# LMS7002M.net
KiCad netlist of a schematic drawn in Altium Designer
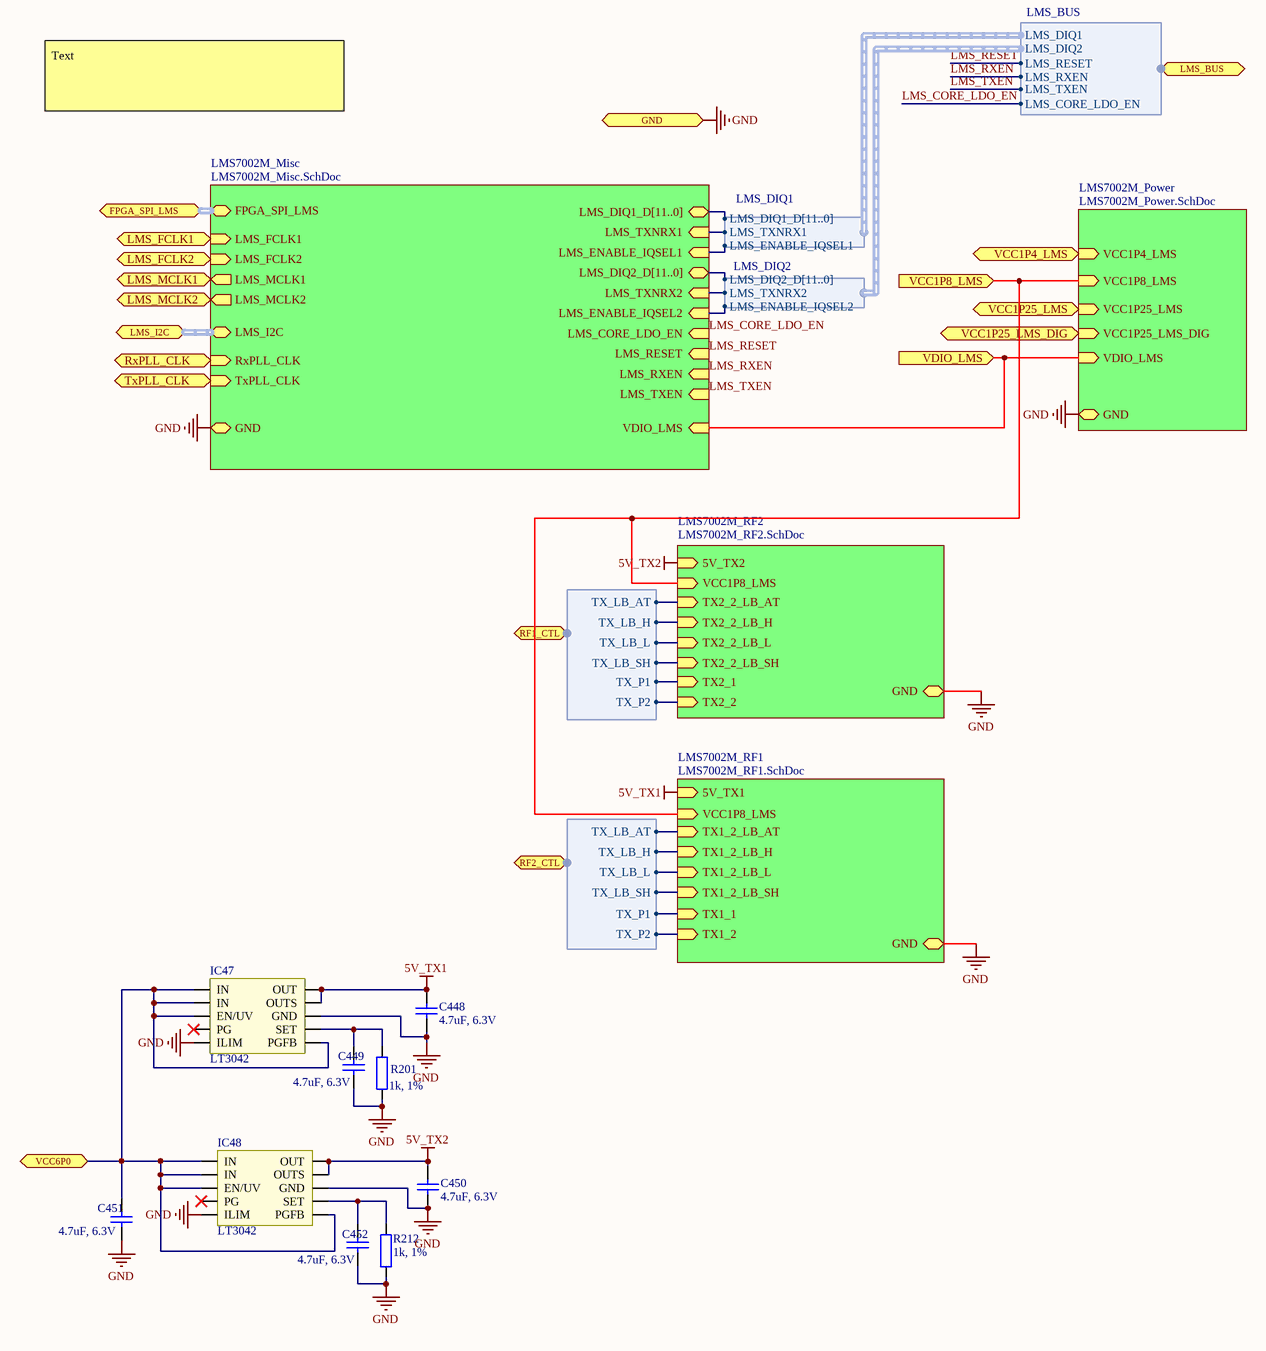
[diagram p0: LMS7002M.SchDoc]

(export (version "E")
  (design (tool "Eeschema 10.0.6"))
  (components
    (comp (ref "C448")
      (value "4.7uF, 6.3V")
      (footprint "CAP0402")
      (fields
        (field (name "MANUFACTURER") "Murata Electronics North America")
        (field (name "TOLERANCE") "±20%")
        (field (name "MANUFACTURER PART NUMBER") "GRM155R60J475ME87D")
      )
      (libsource (lib "LimeMicroAltiumLib_schLib") (part "Cap_0402"))
    )
    (comp (ref "C449")
      (value "4.7uF, 6.3V")
      (footprint "CAP0402")
      (fields
        (field (name "MANUFACTURER") "Murata Electronics North America")
        (field (name "TOLERANCE") "±20%")
        (field (name "MANUFACTURER PART NUMBER") "GRM155R60J475ME87D")
      )
      (libsource (lib "LimeMicroAltiumLib_schLib") (part "Cap_0402"))
    )
    (comp (ref "C450")
      (value "4.7uF, 6.3V")
      (footprint "CAP0402")
      (fields
        (field (name "MANUFACTURER") "Murata Electronics North America")
        (field (name "TOLERANCE") "±20%")
        (field (name "MANUFACTURER PART NUMBER") "GRM155R60J475ME87D")
      )
      (libsource (lib "LimeMicroAltiumLib_schLib") (part "Cap_0402"))
    )
    (comp (ref "C451")
      (value "4.7uF, 6.3V")
      (footprint "CAP0402")
      (fields
        (field (name "MANUFACTURER") "Murata Electronics North America")
        (field (name "TOLERANCE") "±20%")
        (field (name "MANUFACTURER PART NUMBER") "GRM155R60J475ME87D")
      )
      (libsource (lib "LimeMicroAltiumLib_schLib") (part "Cap_0402"))
    )
    (comp (ref "C452")
      (value "4.7uF, 6.3V")
      (footprint "CAP0402")
      (fields
        (field (name "MANUFACTURER") "Murata Electronics North America")
        (field (name "TOLERANCE") "±20%")
        (field (name "MANUFACTURER PART NUMBER") "GRM155R60J475ME87D")
      )
      (libsource (lib "LimeMicroAltiumLib_schLib") (part "Cap_0402"))
    )
    (comp (ref "IC47")
      (value "LT3042")
      (footprint "SOP-10")
      (libsource (lib "LimeMicroAltiumLib_schLib") (part "LT3042"))
    )
    (comp (ref "IC48")
      (value "LT3042")
      (footprint "SOP-10")
      (libsource (lib "LimeMicroAltiumLib_schLib") (part "LT3042"))
    )
    (comp (ref "R201")
      (value "1k, 1%")
      (footprint "RES0402")
      (fields (field (name "MANUFACTURER") "Stackpole Electronics Inc") (field (name "TOLERANCE") "±1%"))
      (libsource (lib "LimeMicroAltiumLib_schLib") (part "Res_0402"))
    )
    (comp (ref "R212")
      (value "1k, 1%")
      (footprint "RES0402")
      (fields (field (name "MANUFACTURER") "Stackpole Electronics Inc") (field (name "TOLERANCE") "±1%"))
      (libsource (lib "LimeMicroAltiumLib_schLib") (part "Res_0402"))
    )
  )
  (nets
    (net (code "41") (name "/VCC6P0") (class "Default")
      (node (ref "C451") (pin "2") (pinfunction "2_2") (pintype "passive"))
      (node (ref "IC47") (pin "1") (pinfunction "IN_1") (pintype "passive"))
      (node (ref "IC47") (pin "2") (pinfunction "IN_2") (pintype "passive"))
      (node (ref "IC47") (pin "3") (pinfunction "EN/UV_3") (pintype "passive"))
      (node (ref "IC47") (pin "6") (pinfunction "PGFB_6") (pintype "passive"))
      (node (ref "IC48") (pin "1") (pinfunction "IN_1") (pintype "passive"))
      (node (ref "IC48") (pin "2") (pinfunction "IN_2") (pintype "passive"))
      (node (ref "IC48") (pin "3") (pinfunction "EN/UV_3") (pintype "passive"))
      (node (ref "IC48") (pin "6") (pinfunction "PGFB_6") (pintype "passive"))
    )
    (net (code "46") (name "5V_TX1") (class "Default")
      (node (ref "C448") (pin "2") (pinfunction "2_2") (pintype "passive"))
      (node (ref "IC47") (pin "10") (pinfunction "OUT_10") (pintype "passive"))
      (node (ref "IC47") (pin "9") (pinfunction "OUTS_9") (pintype "passive"))
    )
    (net (code "47") (name "5V_TX2") (class "Default")
      (node (ref "C450") (pin "2") (pinfunction "2_2") (pintype "passive"))
      (node (ref "IC48") (pin "10") (pinfunction "OUT_10") (pintype "passive"))
      (node (ref "IC48") (pin "9") (pinfunction "OUTS_9") (pintype "passive"))
    )
    (net (code "48") (name "GND") (class "Default")
      (node (ref "C448") (pin "1") (pinfunction "1_1") (pintype "passive"))
      (node (ref "C449") (pin "1") (pinfunction "1_1") (pintype "passive"))
      (node (ref "C450") (pin "1") (pinfunction "1_1") (pintype "passive"))
      (node (ref "C451") (pin "1") (pinfunction "1_1") (pintype "passive"))
      (node (ref "C452") (pin "1") (pinfunction "1_1") (pintype "passive"))
      (node (ref "IC47") (pin "5") (pinfunction "ILIM_5") (pintype "passive"))
      (node (ref "IC47") (pin "8") (pinfunction "GND_8") (pintype "passive"))
      (node (ref "IC48") (pin "5") (pinfunction "ILIM_5") (pintype "passive"))
      (node (ref "IC48") (pin "8") (pinfunction "GND_8") (pintype "passive"))
      (node (ref "R201") (pin "1") (pinfunction "1_1") (pintype "passive"))
      (node (ref "R212") (pin "1") (pinfunction "1_1") (pintype "passive"))
    )
    (net (code "49") (name "Net-(IC47-SET)") (class "Default")
      (node (ref "C449") (pin "2") (pinfunction "2_2") (pintype "passive"))
      (node (ref "IC47") (pin "7") (pinfunction "SET_7") (pintype "passive"))
      (node (ref "R201") (pin "2") (pinfunction "2_2") (pintype "passive"))
    )
    (net (code "50") (name "Net-(IC48-SET)") (class "Default")
      (node (ref "C452") (pin "2") (pinfunction "2_2") (pintype "passive"))
      (node (ref "IC48") (pin "7") (pinfunction "SET_7") (pintype "passive"))
      (node (ref "R212") (pin "2") (pinfunction "2_2") (pintype "passive"))
    )
    (net (code "51") (name "unconnected-(IC47-PG-Pad4)") (class "Default")
      (node (ref "IC47") (pin "4") (pinfunction "PG_4") (pintype "passive+no_connect"))
    )
    (net (code "52") (name "unconnected-(IC48-PG-Pad4)") (class "Default")
      (node (ref "IC48") (pin "4") (pinfunction "PG_4") (pintype "passive+no_connect"))
    )
  )
)
